# Sheet1.net
KiCad netlist of a schematic drawn in Altium Designer
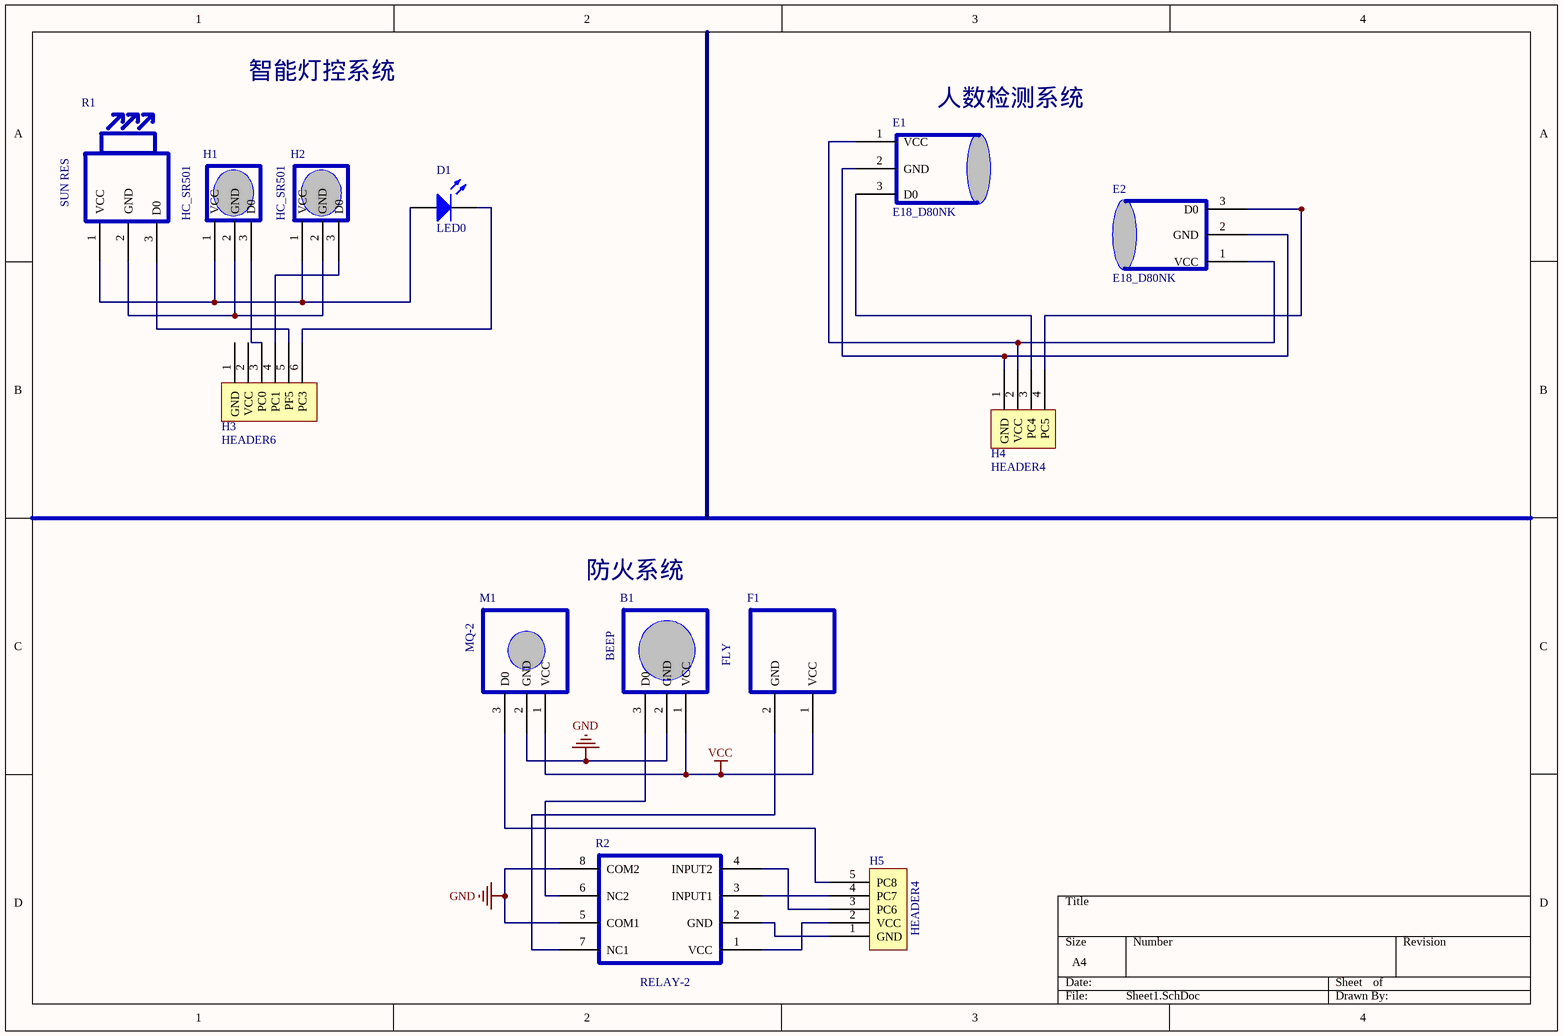
[diagram p0: Sheet1.SchDoc]

(export (version "E")
  (design (tool "Eeschema 10.0.6"))
  (components
    (comp (ref "B1") (value "BEEP") (libsource (lib "Schlib1") (part "BEEP")))
    (comp (ref "D1")
      (value "LED0")
      (footprint "LED-0")
      (description "Typical INFRARED GaAs LED")
      (fields (field (name "PUBLISHER") "Altium Limited"))
      (libsource (lib "Miscellaneous Devices") (part "LED0"))
    )
    (comp (ref "E1") (value "E18_D80NK") (libsource (lib "") (part "E18_D80NK_1")))
    (comp (ref "E2") (value "E18_D80NK") (libsource (lib "Schlib1") (part "E18_D80NK")))
    (comp (ref "F1") (value "FLY") (libsource (lib "Schlib1") (part "FLY")))
    (comp (ref "H1") (value "HC_SR501") (libsource (lib "Schlib1") (part "HC_SR501")))
    (comp (ref "H2") (value "HC_SR501") (libsource (lib "Schlib1") (part "HC_SR501")))
    (comp (ref "H3") (value "HEADER6") (libsource (lib "Schlib1") (part "Header 6")))
    (comp (ref "H4") (value "HEADER4") (libsource (lib "Schlib1") (part "Header 4")))
    (comp (ref "H5") (value "HEADER4") (libsource (lib "Schlib1") (part "Header 4R")))
    (comp (ref "M1") (value "MQ-2") (libsource (lib "Schlib1") (part "MQ-2")))
    (comp (ref "R1") (value "SUN RES") (libsource (lib "Schlib1") (part "RES_SUN")))
    (comp (ref "R2") (value "RELAY-2") (libsource (lib "Schlib1") (part "RELAY-2")))
  )
  (nets
    (net (code "1") (name "GND") (class "Default")
      (node (ref "B1") (pin "2") (pinfunction "GND_2") (pintype "passive"))
      (node (ref "M1") (pin "2") (pinfunction "GND_2") (pintype "passive"))
      (node (ref "R2") (pin "5") (pinfunction "COM1_5") (pintype "passive"))
      (node (ref "R2") (pin "8") (pinfunction "COM2_8") (pintype "passive"))
    )
    (net (code "2") (name "Net-(B1-D0)") (class "Default")
      (node (ref "B1") (pin "3") (pinfunction "D0_3") (pintype "passive"))
      (node (ref "R2") (pin "6") (pinfunction "NC2_6") (pintype "passive"))
    )
    (net (code "3") (name "Net-(D1-A)") (class "Default")
      (node (ref "D1") (pin "1") (pinfunction "A_1") (pintype "passive"))
      (node (ref "H1") (pin "1") (pinfunction "VCC_1") (pintype "passive"))
      (node (ref "H2") (pin "1") (pinfunction "VCC_1") (pintype "passive"))
      (node (ref "R1") (pin "1") (pinfunction "VCC_1") (pintype "passive"))
    )
    (net (code "4") (name "Net-(D1-K)") (class "Default")
      (node (ref "D1") (pin "2") (pinfunction "K_2") (pintype "passive"))
      (node (ref "H3") (pin "6") (pinfunction "PC3_6") (pintype "passive"))
    )
    (net (code "5") (name "Net-(E1-D0)") (class "Default")
      (node (ref "E1") (pin "3") (pinfunction "D0_3") (pintype "passive"))
      (node (ref "H4") (pin "3") (pinfunction "PC4_3") (pintype "passive"))
    )
    (net (code "6") (name "Net-(E1-GND)") (class "Default")
      (node (ref "E1") (pin "2") (pinfunction "GND_2") (pintype "passive"))
      (node (ref "E2") (pin "2") (pinfunction "GND_2") (pintype "passive"))
      (node (ref "H4") (pin "1") (pinfunction "GND_1") (pintype "passive"))
    )
    (net (code "7") (name "Net-(E1-VCC)") (class "Default")
      (node (ref "E1") (pin "1") (pinfunction "VCC_1") (pintype "passive"))
      (node (ref "E2") (pin "1") (pinfunction "VCC_1") (pintype "passive"))
      (node (ref "H4") (pin "2") (pinfunction "VCC_2") (pintype "passive"))
    )
    (net (code "8") (name "Net-(E2-D0)") (class "Default")
      (node (ref "E2") (pin "3") (pinfunction "D0_3") (pintype "passive"))
      (node (ref "H4") (pin "4") (pinfunction "PC5_4") (pintype "passive"))
    )
    (net (code "9") (name "Net-(F1-GND)") (class "Default")
      (node (ref "F1") (pin "2") (pinfunction "GND_2") (pintype "passive"))
      (node (ref "R2") (pin "7") (pinfunction "NC1_7") (pintype "passive"))
    )
    (net (code "10") (name "Net-(H1-D0)") (class "Default")
      (node (ref "H1") (pin "3") (pinfunction "D0_3") (pintype "passive"))
      (node (ref "H3") (pin "3") (pinfunction "PC0_3") (pintype "passive"))
    )
    (net (code "11") (name "Net-(H1-GND)") (class "Default")
      (node (ref "H1") (pin "2") (pinfunction "GND_2") (pintype "passive"))
      (node (ref "H2") (pin "2") (pinfunction "GND_2") (pintype "passive"))
      (node (ref "R1") (pin "2") (pinfunction "GND_2") (pintype "passive"))
    )
    (net (code "12") (name "Net-(H2-D0)") (class "Default")
      (node (ref "H2") (pin "3") (pinfunction "D0_3") (pintype "passive"))
      (node (ref "H3") (pin "4") (pinfunction "PC1_4") (pintype "passive"))
    )
    (net (code "13") (name "Net-(H3-PF5)") (class "Default")
      (node (ref "H3") (pin "5") (pinfunction "PF5_5") (pintype "passive"))
      (node (ref "R1") (pin "3") (pinfunction "D0_3") (pintype "passive"))
    )
    (net (code "14") (name "Net-(H5-GND)") (class "Default")
      (node (ref "H5") (pin "1") (pinfunction "GND_1") (pintype "passive"))
      (node (ref "R2") (pin "2") (pinfunction "GND_2") (pintype "passive"))
    )
    (net (code "15") (name "Net-(H5-PC6)") (class "Default")
      (node (ref "H5") (pin "3") (pinfunction "PC6_3") (pintype "passive"))
      (node (ref "R2") (pin "4") (pinfunction "INPUT2_4") (pintype "passive"))
    )
    (net (code "16") (name "Net-(H5-PC7)") (class "Default")
      (node (ref "H5") (pin "4") (pinfunction "PC7_4") (pintype "passive"))
      (node (ref "R2") (pin "3") (pinfunction "INPUT1_3") (pintype "passive"))
    )
    (net (code "17") (name "Net-(H5-PC8)") (class "Default")
      (node (ref "H5") (pin "5") (pinfunction "PC8_5") (pintype "passive"))
      (node (ref "M1") (pin "3") (pinfunction "D0_3") (pintype "passive"))
    )
    (net (code "18") (name "Net-(H5-VCC)") (class "Default")
      (node (ref "H5") (pin "2") (pinfunction "VCC_2") (pintype "passive"))
      (node (ref "R2") (pin "1") (pinfunction "VCC_1") (pintype "passive"))
    )
    (net (code "19") (name "VCC") (class "Default")
      (node (ref "B1") (pin "1") (pinfunction "VCC_1") (pintype "passive"))
      (node (ref "F1") (pin "1") (pinfunction "VCC_1") (pintype "passive"))
      (node (ref "M1") (pin "1") (pinfunction "VCC_1") (pintype "passive"))
    )
    (net (code "20") (name "unconnected-(H3-GND-Pad1)") (class "Default")
      (node (ref "H3") (pin "1") (pinfunction "GND_1") (pintype "passive"))
    )
    (net (code "21") (name "unconnected-(H3-VCC-Pad2)") (class "Default")
      (node (ref "H3") (pin "2") (pinfunction "VCC_2") (pintype "passive"))
    )
  )
)
